# Sheet1.net
KiCad netlist of a schematic drawn in Altium Designer
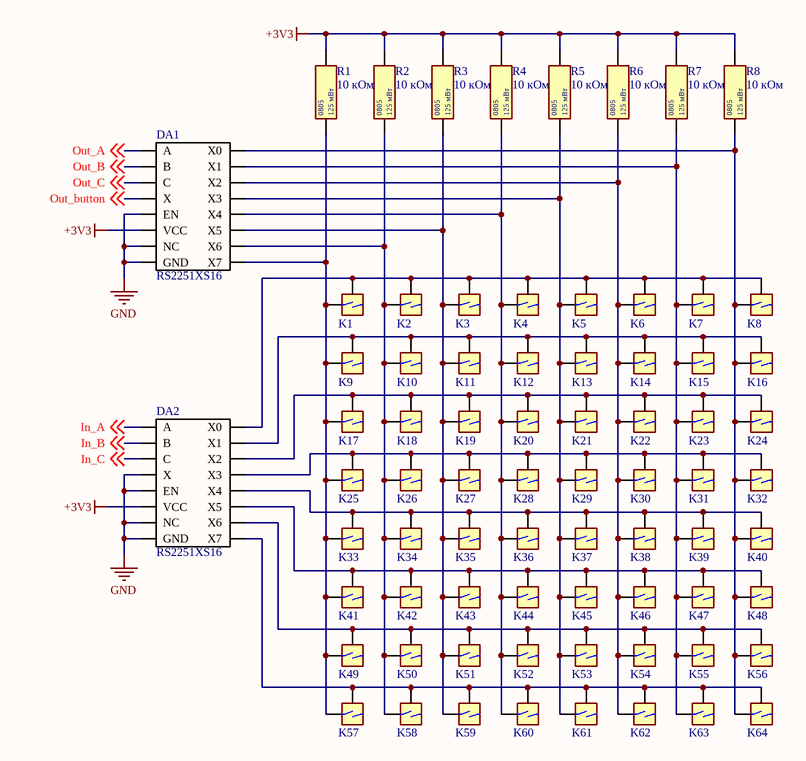
[diagram p0: Sheet1.SchDoc]

(export (version "E")
  (design (tool "Eeschema 10.0.6"))
  (components
    (comp (ref "DA1")
      (value "RS2251XS16")
      (footprint "SOIC-16 - duplicate")
      (description "Мультиплексор 8ch RS2251XS16, SOIC-16")
      (libsource (lib "Schlib") (part "RS2251XS16"))
    )
    (comp (ref "DA2")
      (value "RS2251XS16")
      (footprint "SOIC-16 - duplicate")
      (description "Мультиплексор 8ch RS2251XS16, SOIC-16")
      (libsource (lib "Schlib") (part "RS2251XS16"))
    )
    (comp (ref "K1")
      (value "Геркон")
      (footprint "Gerkon_11x25")
      (libsource (lib "Schlib") (part "1402 10-20AT"))
    )
    (comp (ref "K2")
      (value "Геркон")
      (footprint "Gerkon_11x25")
      (libsource (lib "Schlib") (part "1402 10-20AT"))
    )
    (comp (ref "K3")
      (value "Геркон")
      (footprint "Gerkon_11x25")
      (libsource (lib "Schlib") (part "1402 10-20AT"))
    )
    (comp (ref "K4")
      (value "Геркон")
      (footprint "Gerkon_11x25")
      (libsource (lib "Schlib") (part "1402 10-20AT"))
    )
    (comp (ref "K5")
      (value "Геркон")
      (footprint "Gerkon_11x25")
      (libsource (lib "Schlib") (part "1402 10-20AT"))
    )
    (comp (ref "K6")
      (value "Геркон")
      (footprint "Gerkon_11x25")
      (libsource (lib "Schlib") (part "1402 10-20AT"))
    )
    (comp (ref "K7")
      (value "Геркон")
      (footprint "Gerkon_11x25")
      (libsource (lib "Schlib") (part "1402 10-20AT"))
    )
    (comp (ref "K8")
      (value "Геркон")
      (footprint "Gerkon_11x25")
      (libsource (lib "Schlib") (part "1402 10-20AT"))
    )
    (comp (ref "K9")
      (value "Геркон")
      (footprint "Gerkon_11x25")
      (libsource (lib "Schlib") (part "1402 10-20AT"))
    )
    (comp (ref "K10")
      (value "Геркон")
      (footprint "Gerkon_11x25")
      (libsource (lib "Schlib") (part "1402 10-20AT"))
    )
    (comp (ref "K11")
      (value "Геркон")
      (footprint "Gerkon_11x25")
      (libsource (lib "Schlib") (part "1402 10-20AT"))
    )
    (comp (ref "K12")
      (value "Геркон")
      (footprint "Gerkon_11x25")
      (libsource (lib "Schlib") (part "1402 10-20AT"))
    )
    (comp (ref "K13")
      (value "Геркон")
      (footprint "Gerkon_11x25")
      (libsource (lib "Schlib") (part "1402 10-20AT"))
    )
    (comp (ref "K14")
      (value "Геркон")
      (footprint "Gerkon_11x25")
      (libsource (lib "Schlib") (part "1402 10-20AT"))
    )
    (comp (ref "K15")
      (value "Геркон")
      (footprint "Gerkon_11x25")
      (libsource (lib "Schlib") (part "1402 10-20AT"))
    )
    (comp (ref "K16")
      (value "Геркон")
      (footprint "Gerkon_11x25")
      (libsource (lib "Schlib") (part "1402 10-20AT"))
    )
    (comp (ref "K17")
      (value "Геркон")
      (footprint "Gerkon_11x25")
      (libsource (lib "Schlib") (part "1402 10-20AT"))
    )
    (comp (ref "K18")
      (value "Геркон")
      (footprint "Gerkon_11x25")
      (libsource (lib "Schlib") (part "1402 10-20AT"))
    )
    (comp (ref "K19")
      (value "Геркон")
      (footprint "Gerkon_11x25")
      (libsource (lib "Schlib") (part "1402 10-20AT"))
    )
    (comp (ref "K20")
      (value "Геркон")
      (footprint "Gerkon_11x25")
      (libsource (lib "Schlib") (part "1402 10-20AT"))
    )
    (comp (ref "K21")
      (value "Геркон")
      (footprint "Gerkon_11x25")
      (libsource (lib "Schlib") (part "1402 10-20AT"))
    )
    (comp (ref "K22")
      (value "Геркон")
      (footprint "Gerkon_11x25")
      (libsource (lib "Schlib") (part "1402 10-20AT"))
    )
    (comp (ref "K23")
      (value "Геркон")
      (footprint "Gerkon_11x25")
      (libsource (lib "Schlib") (part "1402 10-20AT"))
    )
    (comp (ref "K24")
      (value "Геркон")
      (footprint "Gerkon_11x25")
      (libsource (lib "Schlib") (part "1402 10-20AT"))
    )
    (comp (ref "K25")
      (value "Геркон")
      (footprint "Gerkon_11x25")
      (libsource (lib "Schlib") (part "1402 10-20AT"))
    )
    (comp (ref "K26")
      (value "Геркон")
      (footprint "Gerkon_11x25")
      (libsource (lib "Schlib") (part "1402 10-20AT"))
    )
    (comp (ref "K27")
      (value "Геркон")
      (footprint "Gerkon_11x25")
      (libsource (lib "Schlib") (part "1402 10-20AT"))
    )
    (comp (ref "K28")
      (value "Геркон")
      (footprint "Gerkon_11x25")
      (libsource (lib "Schlib") (part "1402 10-20AT"))
    )
    (comp (ref "K29")
      (value "Геркон")
      (footprint "Gerkon_11x25")
      (libsource (lib "Schlib") (part "1402 10-20AT"))
    )
    (comp (ref "K30")
      (value "Геркон")
      (footprint "Gerkon_11x25")
      (libsource (lib "Schlib") (part "1402 10-20AT"))
    )
    (comp (ref "K31")
      (value "Геркон")
      (footprint "Gerkon_11x25")
      (libsource (lib "Schlib") (part "1402 10-20AT"))
    )
    (comp (ref "K32")
      (value "Геркон")
      (footprint "Gerkon_11x25")
      (libsource (lib "Schlib") (part "1402 10-20AT"))
    )
    (comp (ref "K33")
      (value "Геркон")
      (footprint "Gerkon_11x25")
      (libsource (lib "Schlib") (part "1402 10-20AT"))
    )
    (comp (ref "K34")
      (value "Геркон")
      (footprint "Gerkon_11x25")
      (libsource (lib "Schlib") (part "1402 10-20AT"))
    )
    (comp (ref "K35")
      (value "Геркон")
      (footprint "Gerkon_11x25")
      (libsource (lib "Schlib") (part "1402 10-20AT"))
    )
    (comp (ref "K36")
      (value "Геркон")
      (footprint "Gerkon_11x25")
      (libsource (lib "Schlib") (part "1402 10-20AT"))
    )
    (comp (ref "K37")
      (value "Геркон")
      (footprint "Gerkon_11x25")
      (libsource (lib "Schlib") (part "1402 10-20AT"))
    )
    (comp (ref "K38")
      (value "Геркон")
      (footprint "Gerkon_11x25")
      (libsource (lib "Schlib") (part "1402 10-20AT"))
    )
    (comp (ref "K39")
      (value "Геркон")
      (footprint "Gerkon_11x25")
      (libsource (lib "Schlib") (part "1402 10-20AT"))
    )
    (comp (ref "K40")
      (value "Геркон")
      (footprint "Gerkon_11x25")
      (libsource (lib "Schlib") (part "1402 10-20AT"))
    )
    (comp (ref "K41")
      (value "Геркон")
      (footprint "Gerkon_11x25")
      (libsource (lib "Schlib") (part "1402 10-20AT"))
    )
    (comp (ref "K42")
      (value "Геркон")
      (footprint "Gerkon_11x25")
      (libsource (lib "Schlib") (part "1402 10-20AT"))
    )
    (comp (ref "K43")
      (value "Геркон")
      (footprint "Gerkon_11x25")
      (libsource (lib "Schlib") (part "1402 10-20AT"))
    )
    (comp (ref "K44")
      (value "Геркон")
      (footprint "Gerkon_11x25")
      (libsource (lib "Schlib") (part "1402 10-20AT"))
    )
    (comp (ref "K45")
      (value "Геркон")
      (footprint "Gerkon_11x25")
      (libsource (lib "Schlib") (part "1402 10-20AT"))
    )
    (comp (ref "K46")
      (value "Геркон")
      (footprint "Gerkon_11x25")
      (libsource (lib "Schlib") (part "1402 10-20AT"))
    )
    (comp (ref "K47")
      (value "Геркон")
      (footprint "Gerkon_11x25")
      (libsource (lib "Schlib") (part "1402 10-20AT"))
    )
    (comp (ref "K48")
      (value "Геркон")
      (footprint "Gerkon_11x25")
      (libsource (lib "Schlib") (part "1402 10-20AT"))
    )
    (comp (ref "K49")
      (value "Геркон")
      (footprint "Gerkon_11x25")
      (libsource (lib "Schlib") (part "1402 10-20AT"))
    )
    (comp (ref "K50")
      (value "Геркон")
      (footprint "Gerkon_11x25")
      (libsource (lib "Schlib") (part "1402 10-20AT"))
    )
    (comp (ref "K51")
      (value "Геркон")
      (footprint "Gerkon_11x25")
      (libsource (lib "Schlib") (part "1402 10-20AT"))
    )
    (comp (ref "K52")
      (value "Геркон")
      (footprint "Gerkon_11x25")
      (libsource (lib "Schlib") (part "1402 10-20AT"))
    )
    (comp (ref "K53")
      (value "Геркон")
      (footprint "Gerkon_11x25")
      (libsource (lib "Schlib") (part "1402 10-20AT"))
    )
    (comp (ref "K54")
      (value "Геркон")
      (footprint "Gerkon_11x25")
      (libsource (lib "Schlib") (part "1402 10-20AT"))
    )
    (comp (ref "K55")
      (value "Геркон")
      (footprint "Gerkon_11x25")
      (libsource (lib "Schlib") (part "1402 10-20AT"))
    )
    (comp (ref "K56")
      (value "Геркон")
      (footprint "Gerkon_11x25")
      (libsource (lib "Schlib") (part "1402 10-20AT"))
    )
    (comp (ref "K57")
      (value "Геркон")
      (footprint "Gerkon_11x25")
      (libsource (lib "Schlib") (part "1402 10-20AT"))
    )
    (comp (ref "K58")
      (value "Геркон")
      (footprint "Gerkon_11x25")
      (libsource (lib "Schlib") (part "1402 10-20AT"))
    )
    (comp (ref "K59")
      (value "Геркон")
      (footprint "Gerkon_11x25")
      (libsource (lib "Schlib") (part "1402 10-20AT"))
    )
    (comp (ref "K60")
      (value "Геркон")
      (footprint "Gerkon_11x25")
      (libsource (lib "Schlib") (part "1402 10-20AT"))
    )
    (comp (ref "K61")
      (value "Геркон")
      (footprint "Gerkon_11x25")
      (libsource (lib "Schlib") (part "1402 10-20AT"))
    )
    (comp (ref "K62")
      (value "Геркон")
      (footprint "Gerkon_11x25")
      (libsource (lib "Schlib") (part "1402 10-20AT"))
    )
    (comp (ref "K63")
      (value "Геркон")
      (footprint "Gerkon_11x25")
      (libsource (lib "Schlib") (part "1402 10-20AT"))
    )
    (comp (ref "K64")
      (value "Геркон")
      (footprint "Gerkon_11x25")
      (libsource (lib "Schlib") (part "1402 10-20AT"))
    )
    (comp (ref "R1")
      (value "10 кОм")
      (footprint "R-0805")
      (description "Резистор 0805 5% 10 кОм")
      (libsource (lib "Schlib") (part "RC0805JR-0710KL"))
    )
    (comp (ref "R2")
      (value "10 кОм")
      (footprint "R-0805")
      (description "Резистор 0805 5% 10 кОм")
      (libsource (lib "Schlib") (part "RC0805JR-0710KL"))
    )
    (comp (ref "R3")
      (value "10 кОм")
      (footprint "R-0805")
      (description "Резистор 0805 5% 10 кОм")
      (libsource (lib "Schlib") (part "RC0805JR-0710KL"))
    )
    (comp (ref "R4")
      (value "10 кОм")
      (footprint "R-0805")
      (description "Резистор 0805 5% 10 кОм")
      (libsource (lib "Schlib") (part "RC0805JR-0710KL"))
    )
    (comp (ref "R5")
      (value "10 кОм")
      (footprint "R-0805")
      (description "Резистор 0805 5% 10 кОм")
      (libsource (lib "Schlib") (part "RC0805JR-0710KL"))
    )
    (comp (ref "R6")
      (value "10 кОм")
      (footprint "R-0805")
      (description "Резистор 0805 5% 10 кОм")
      (libsource (lib "Schlib") (part "RC0805JR-0710KL"))
    )
    (comp (ref "R7")
      (value "10 кОм")
      (footprint "R-0805")
      (description "Резистор 0805 5% 10 кОм")
      (libsource (lib "Schlib") (part "RC0805JR-0710KL"))
    )
    (comp (ref "R8")
      (value "10 кОм")
      (footprint "R-0805")
      (description "Резистор 0805 5% 10 кОм")
      (libsource (lib "Schlib") (part "RC0805JR-0710KL"))
    )
  )
  (nets
    (net (code "1") (name "+3V3") (class "Default")
      (node (ref "DA1") (pin "16") (pinfunction "VCC_16") (pintype "passive"))
      (node (ref "DA2") (pin "16") (pinfunction "VCC_16") (pintype "passive"))
      (node (ref "R1") (pin "2") (pinfunction "2_2") (pintype "passive"))
      (node (ref "R2") (pin "2") (pinfunction "2_2") (pintype "passive"))
      (node (ref "R3") (pin "2") (pinfunction "2_2") (pintype "passive"))
      (node (ref "R4") (pin "2") (pinfunction "2_2") (pintype "passive"))
      (node (ref "R5") (pin "2") (pinfunction "2_2") (pintype "passive"))
      (node (ref "R6") (pin "2") (pinfunction "2_2") (pintype "passive"))
      (node (ref "R7") (pin "2") (pinfunction "2_2") (pintype "passive"))
      (node (ref "R8") (pin "2") (pinfunction "2_2") (pintype "passive"))
    )
    (net (code "2") (name "GND") (class "Default")
      (node (ref "DA1") (pin "6") (pinfunction "EN_6") (pintype "passive"))
      (node (ref "DA1") (pin "7") (pinfunction "NC_7") (pintype "passive"))
      (node (ref "DA1") (pin "8") (pinfunction "GND_8") (pintype "passive"))
      (node (ref "DA2") (pin "3") (pinfunction "X_3") (pintype "passive"))
      (node (ref "DA2") (pin "6") (pinfunction "EN_6") (pintype "passive"))
      (node (ref "DA2") (pin "7") (pinfunction "NC_7") (pintype "passive"))
      (node (ref "DA2") (pin "8") (pinfunction "GND_8") (pintype "passive"))
    )
    (net (code "3") (name "In_A") (class "Default")
      (node (ref "DA2") (pin "11") (pinfunction "A_11") (pintype "passive"))
    )
    (net (code "4") (name "In_B") (class "Default")
      (node (ref "DA2") (pin "10") (pinfunction "B_10") (pintype "passive"))
    )
    (net (code "5") (name "In_C") (class "Default")
      (node (ref "DA2") (pin "9") (pinfunction "C_9") (pintype "passive"))
    )
    (net (code "6") (name "Net-(DA1-X0)") (class "Default")
      (node (ref "DA1") (pin "13") (pinfunction "X0_13") (pintype "passive"))
      (node (ref "K16") (pin "1") (pinfunction "1_1") (pintype "passive"))
      (node (ref "K24") (pin "1") (pinfunction "1_1") (pintype "passive"))
      (node (ref "K32") (pin "1") (pinfunction "1_1") (pintype "passive"))
      (node (ref "K40") (pin "1") (pinfunction "1_1") (pintype "passive"))
      (node (ref "K48") (pin "1") (pinfunction "1_1") (pintype "passive"))
      (node (ref "K56") (pin "1") (pinfunction "1_1") (pintype "passive"))
      (node (ref "K64") (pin "1") (pinfunction "1_1") (pintype "passive"))
      (node (ref "K8") (pin "1") (pinfunction "1_1") (pintype "passive"))
      (node (ref "R8") (pin "1") (pinfunction "1_1") (pintype "passive"))
    )
    (net (code "7") (name "Net-(DA1-X1)") (class "Default")
      (node (ref "DA1") (pin "14") (pinfunction "X1_14") (pintype "passive"))
      (node (ref "K15") (pin "1") (pinfunction "1_1") (pintype "passive"))
      (node (ref "K23") (pin "1") (pinfunction "1_1") (pintype "passive"))
      (node (ref "K31") (pin "1") (pinfunction "1_1") (pintype "passive"))
      (node (ref "K39") (pin "1") (pinfunction "1_1") (pintype "passive"))
      (node (ref "K47") (pin "1") (pinfunction "1_1") (pintype "passive"))
      (node (ref "K55") (pin "1") (pinfunction "1_1") (pintype "passive"))
      (node (ref "K63") (pin "1") (pinfunction "1_1") (pintype "passive"))
      (node (ref "K7") (pin "1") (pinfunction "1_1") (pintype "passive"))
      (node (ref "R7") (pin "1") (pinfunction "1_1") (pintype "passive"))
    )
    (net (code "8") (name "Net-(DA1-X2)") (class "Default")
      (node (ref "DA1") (pin "15") (pinfunction "X2_15") (pintype "passive"))
      (node (ref "K14") (pin "1") (pinfunction "1_1") (pintype "passive"))
      (node (ref "K22") (pin "1") (pinfunction "1_1") (pintype "passive"))
      (node (ref "K30") (pin "1") (pinfunction "1_1") (pintype "passive"))
      (node (ref "K38") (pin "1") (pinfunction "1_1") (pintype "passive"))
      (node (ref "K46") (pin "1") (pinfunction "1_1") (pintype "passive"))
      (node (ref "K54") (pin "1") (pinfunction "1_1") (pintype "passive"))
      (node (ref "K6") (pin "1") (pinfunction "1_1") (pintype "passive"))
      (node (ref "K62") (pin "1") (pinfunction "1_1") (pintype "passive"))
      (node (ref "R6") (pin "1") (pinfunction "1_1") (pintype "passive"))
    )
    (net (code "9") (name "Net-(DA1-X3)") (class "Default")
      (node (ref "DA1") (pin "12") (pinfunction "X3_12") (pintype "passive"))
      (node (ref "K13") (pin "1") (pinfunction "1_1") (pintype "passive"))
      (node (ref "K21") (pin "1") (pinfunction "1_1") (pintype "passive"))
      (node (ref "K29") (pin "1") (pinfunction "1_1") (pintype "passive"))
      (node (ref "K37") (pin "1") (pinfunction "1_1") (pintype "passive"))
      (node (ref "K45") (pin "1") (pinfunction "1_1") (pintype "passive"))
      (node (ref "K5") (pin "1") (pinfunction "1_1") (pintype "passive"))
      (node (ref "K53") (pin "1") (pinfunction "1_1") (pintype "passive"))
      (node (ref "K61") (pin "1") (pinfunction "1_1") (pintype "passive"))
      (node (ref "R5") (pin "1") (pinfunction "1_1") (pintype "passive"))
    )
    (net (code "10") (name "Net-(DA1-X4)") (class "Default")
      (node (ref "DA1") (pin "1") (pinfunction "X4_1") (pintype "passive"))
      (node (ref "K12") (pin "1") (pinfunction "1_1") (pintype "passive"))
      (node (ref "K20") (pin "1") (pinfunction "1_1") (pintype "passive"))
      (node (ref "K28") (pin "1") (pinfunction "1_1") (pintype "passive"))
      (node (ref "K36") (pin "1") (pinfunction "1_1") (pintype "passive"))
      (node (ref "K4") (pin "1") (pinfunction "1_1") (pintype "passive"))
      (node (ref "K44") (pin "1") (pinfunction "1_1") (pintype "passive"))
      (node (ref "K52") (pin "1") (pinfunction "1_1") (pintype "passive"))
      (node (ref "K60") (pin "1") (pinfunction "1_1") (pintype "passive"))
      (node (ref "R4") (pin "1") (pinfunction "1_1") (pintype "passive"))
    )
    (net (code "11") (name "Net-(DA1-X5)") (class "Default")
      (node (ref "DA1") (pin "5") (pinfunction "X5_5") (pintype "passive"))
      (node (ref "K11") (pin "1") (pinfunction "1_1") (pintype "passive"))
      (node (ref "K19") (pin "1") (pinfunction "1_1") (pintype "passive"))
      (node (ref "K27") (pin "1") (pinfunction "1_1") (pintype "passive"))
      (node (ref "K3") (pin "1") (pinfunction "1_1") (pintype "passive"))
      (node (ref "K35") (pin "1") (pinfunction "1_1") (pintype "passive"))
      (node (ref "K43") (pin "1") (pinfunction "1_1") (pintype "passive"))
      (node (ref "K51") (pin "1") (pinfunction "1_1") (pintype "passive"))
      (node (ref "K59") (pin "1") (pinfunction "1_1") (pintype "passive"))
      (node (ref "R3") (pin "1") (pinfunction "1_1") (pintype "passive"))
    )
    (net (code "12") (name "Net-(DA1-X6)") (class "Default")
      (node (ref "DA1") (pin "2") (pinfunction "X6_2") (pintype "passive"))
      (node (ref "K10") (pin "1") (pinfunction "1_1") (pintype "passive"))
      (node (ref "K18") (pin "1") (pinfunction "1_1") (pintype "passive"))
      (node (ref "K2") (pin "1") (pinfunction "1_1") (pintype "passive"))
      (node (ref "K26") (pin "1") (pinfunction "1_1") (pintype "passive"))
      (node (ref "K34") (pin "1") (pinfunction "1_1") (pintype "passive"))
      (node (ref "K42") (pin "1") (pinfunction "1_1") (pintype "passive"))
      (node (ref "K50") (pin "1") (pinfunction "1_1") (pintype "passive"))
      (node (ref "K58") (pin "1") (pinfunction "1_1") (pintype "passive"))
      (node (ref "R2") (pin "1") (pinfunction "1_1") (pintype "passive"))
    )
    (net (code "13") (name "Net-(DA1-X7)") (class "Default")
      (node (ref "DA1") (pin "4") (pinfunction "X7_4") (pintype "passive"))
      (node (ref "K1") (pin "1") (pinfunction "1_1") (pintype "passive"))
      (node (ref "K17") (pin "1") (pinfunction "1_1") (pintype "passive"))
      (node (ref "K25") (pin "1") (pinfunction "1_1") (pintype "passive"))
      (node (ref "K33") (pin "1") (pinfunction "1_1") (pintype "passive"))
      (node (ref "K41") (pin "1") (pinfunction "1_1") (pintype "passive"))
      (node (ref "K49") (pin "1") (pinfunction "1_1") (pintype "passive"))
      (node (ref "K57") (pin "1") (pinfunction "1_1") (pintype "passive"))
      (node (ref "K9") (pin "1") (pinfunction "1_1") (pintype "passive"))
      (node (ref "R1") (pin "1") (pinfunction "1_1") (pintype "passive"))
    )
    (net (code "14") (name "Net-(DA2-X0)") (class "Default")
      (node (ref "DA2") (pin "13") (pinfunction "X0_13") (pintype "passive"))
      (node (ref "K1") (pin "2") (pinfunction "2_2") (pintype "passive"))
      (node (ref "K2") (pin "2") (pinfunction "2_2") (pintype "passive"))
      (node (ref "K3") (pin "2") (pinfunction "2_2") (pintype "passive"))
      (node (ref "K4") (pin "2") (pinfunction "2_2") (pintype "passive"))
      (node (ref "K5") (pin "2") (pinfunction "2_2") (pintype "passive"))
      (node (ref "K6") (pin "2") (pinfunction "2_2") (pintype "passive"))
      (node (ref "K7") (pin "2") (pinfunction "2_2") (pintype "passive"))
      (node (ref "K8") (pin "2") (pinfunction "2_2") (pintype "passive"))
    )
    (net (code "15") (name "Net-(DA2-X1)") (class "Default")
      (node (ref "DA2") (pin "14") (pinfunction "X1_14") (pintype "passive"))
      (node (ref "K10") (pin "2") (pinfunction "2_2") (pintype "passive"))
      (node (ref "K11") (pin "2") (pinfunction "2_2") (pintype "passive"))
      (node (ref "K12") (pin "2") (pinfunction "2_2") (pintype "passive"))
      (node (ref "K13") (pin "2") (pinfunction "2_2") (pintype "passive"))
      (node (ref "K14") (pin "2") (pinfunction "2_2") (pintype "passive"))
      (node (ref "K15") (pin "2") (pinfunction "2_2") (pintype "passive"))
      (node (ref "K16") (pin "2") (pinfunction "2_2") (pintype "passive"))
      (node (ref "K9") (pin "2") (pinfunction "2_2") (pintype "passive"))
    )
    (net (code "16") (name "Net-(DA2-X2)") (class "Default")
      (node (ref "DA2") (pin "15") (pinfunction "X2_15") (pintype "passive"))
      (node (ref "K17") (pin "2") (pinfunction "2_2") (pintype "passive"))
      (node (ref "K18") (pin "2") (pinfunction "2_2") (pintype "passive"))
      (node (ref "K19") (pin "2") (pinfunction "2_2") (pintype "passive"))
      (node (ref "K20") (pin "2") (pinfunction "2_2") (pintype "passive"))
      (node (ref "K21") (pin "2") (pinfunction "2_2") (pintype "passive"))
      (node (ref "K22") (pin "2") (pinfunction "2_2") (pintype "passive"))
      (node (ref "K23") (pin "2") (pinfunction "2_2") (pintype "passive"))
      (node (ref "K24") (pin "2") (pinfunction "2_2") (pintype "passive"))
    )
    (net (code "17") (name "Net-(DA2-X3)") (class "Default")
      (node (ref "DA2") (pin "12") (pinfunction "X3_12") (pintype "passive"))
      (node (ref "K25") (pin "2") (pinfunction "2_2") (pintype "passive"))
      (node (ref "K26") (pin "2") (pinfunction "2_2") (pintype "passive"))
      (node (ref "K27") (pin "2") (pinfunction "2_2") (pintype "passive"))
      (node (ref "K28") (pin "2") (pinfunction "2_2") (pintype "passive"))
      (node (ref "K29") (pin "2") (pinfunction "2_2") (pintype "passive"))
      (node (ref "K30") (pin "2") (pinfunction "2_2") (pintype "passive"))
      (node (ref "K31") (pin "2") (pinfunction "2_2") (pintype "passive"))
      (node (ref "K32") (pin "2") (pinfunction "2_2") (pintype "passive"))
    )
    (net (code "18") (name "Net-(DA2-X4)") (class "Default")
      (node (ref "DA2") (pin "1") (pinfunction "X4_1") (pintype "passive"))
      (node (ref "K33") (pin "2") (pinfunction "2_2") (pintype "passive"))
      (node (ref "K34") (pin "2") (pinfunction "2_2") (pintype "passive"))
      (node (ref "K35") (pin "2") (pinfunction "2_2") (pintype "passive"))
      (node (ref "K36") (pin "2") (pinfunction "2_2") (pintype "passive"))
      (node (ref "K37") (pin "2") (pinfunction "2_2") (pintype "passive"))
      (node (ref "K38") (pin "2") (pinfunction "2_2") (pintype "passive"))
      (node (ref "K39") (pin "2") (pinfunction "2_2") (pintype "passive"))
      (node (ref "K40") (pin "2") (pinfunction "2_2") (pintype "passive"))
    )
    (net (code "19") (name "Net-(DA2-X5)") (class "Default")
      (node (ref "DA2") (pin "5") (pinfunction "X5_5") (pintype "passive"))
      (node (ref "K41") (pin "2") (pinfunction "2_2") (pintype "passive"))
      (node (ref "K42") (pin "2") (pinfunction "2_2") (pintype "passive"))
      (node (ref "K43") (pin "2") (pinfunction "2_2") (pintype "passive"))
      (node (ref "K44") (pin "2") (pinfunction "2_2") (pintype "passive"))
      (node (ref "K45") (pin "2") (pinfunction "2_2") (pintype "passive"))
      (node (ref "K46") (pin "2") (pinfunction "2_2") (pintype "passive"))
      (node (ref "K47") (pin "2") (pinfunction "2_2") (pintype "passive"))
      (node (ref "K48") (pin "2") (pinfunction "2_2") (pintype "passive"))
    )
    (net (code "20") (name "Net-(DA2-X6)") (class "Default")
      (node (ref "DA2") (pin "2") (pinfunction "X6_2") (pintype "passive"))
      (node (ref "K49") (pin "2") (pinfunction "2_2") (pintype "passive"))
      (node (ref "K50") (pin "2") (pinfunction "2_2") (pintype "passive"))
      (node (ref "K51") (pin "2") (pinfunction "2_2") (pintype "passive"))
      (node (ref "K52") (pin "2") (pinfunction "2_2") (pintype "passive"))
      (node (ref "K53") (pin "2") (pinfunction "2_2") (pintype "passive"))
      (node (ref "K54") (pin "2") (pinfunction "2_2") (pintype "passive"))
      (node (ref "K55") (pin "2") (pinfunction "2_2") (pintype "passive"))
      (node (ref "K56") (pin "2") (pinfunction "2_2") (pintype "passive"))
    )
    (net (code "21") (name "Net-(DA2-X7)") (class "Default")
      (node (ref "DA2") (pin "4") (pinfunction "X7_4") (pintype "passive"))
      (node (ref "K57") (pin "2") (pinfunction "2_2") (pintype "passive"))
      (node (ref "K58") (pin "2") (pinfunction "2_2") (pintype "passive"))
      (node (ref "K59") (pin "2") (pinfunction "2_2") (pintype "passive"))
      (node (ref "K60") (pin "2") (pinfunction "2_2") (pintype "passive"))
      (node (ref "K61") (pin "2") (pinfunction "2_2") (pintype "passive"))
      (node (ref "K62") (pin "2") (pinfunction "2_2") (pintype "passive"))
      (node (ref "K63") (pin "2") (pinfunction "2_2") (pintype "passive"))
      (node (ref "K64") (pin "2") (pinfunction "2_2") (pintype "passive"))
    )
    (net (code "22") (name "Out_A") (class "Default")
      (node (ref "DA1") (pin "11") (pinfunction "A_11") (pintype "passive"))
    )
    (net (code "23") (name "Out_B") (class "Default")
      (node (ref "DA1") (pin "10") (pinfunction "B_10") (pintype "passive"))
    )
    (net (code "24") (name "Out_C") (class "Default")
      (node (ref "DA1") (pin "9") (pinfunction "C_9") (pintype "passive"))
    )
    (net (code "25") (name "Out_button") (class "Default")
      (node (ref "DA1") (pin "3") (pinfunction "X_3") (pintype "passive"))
    )
  )
)
